# SMPS_2018_09_04_A.net
KiCad netlist of a schematic drawn in EAGLE
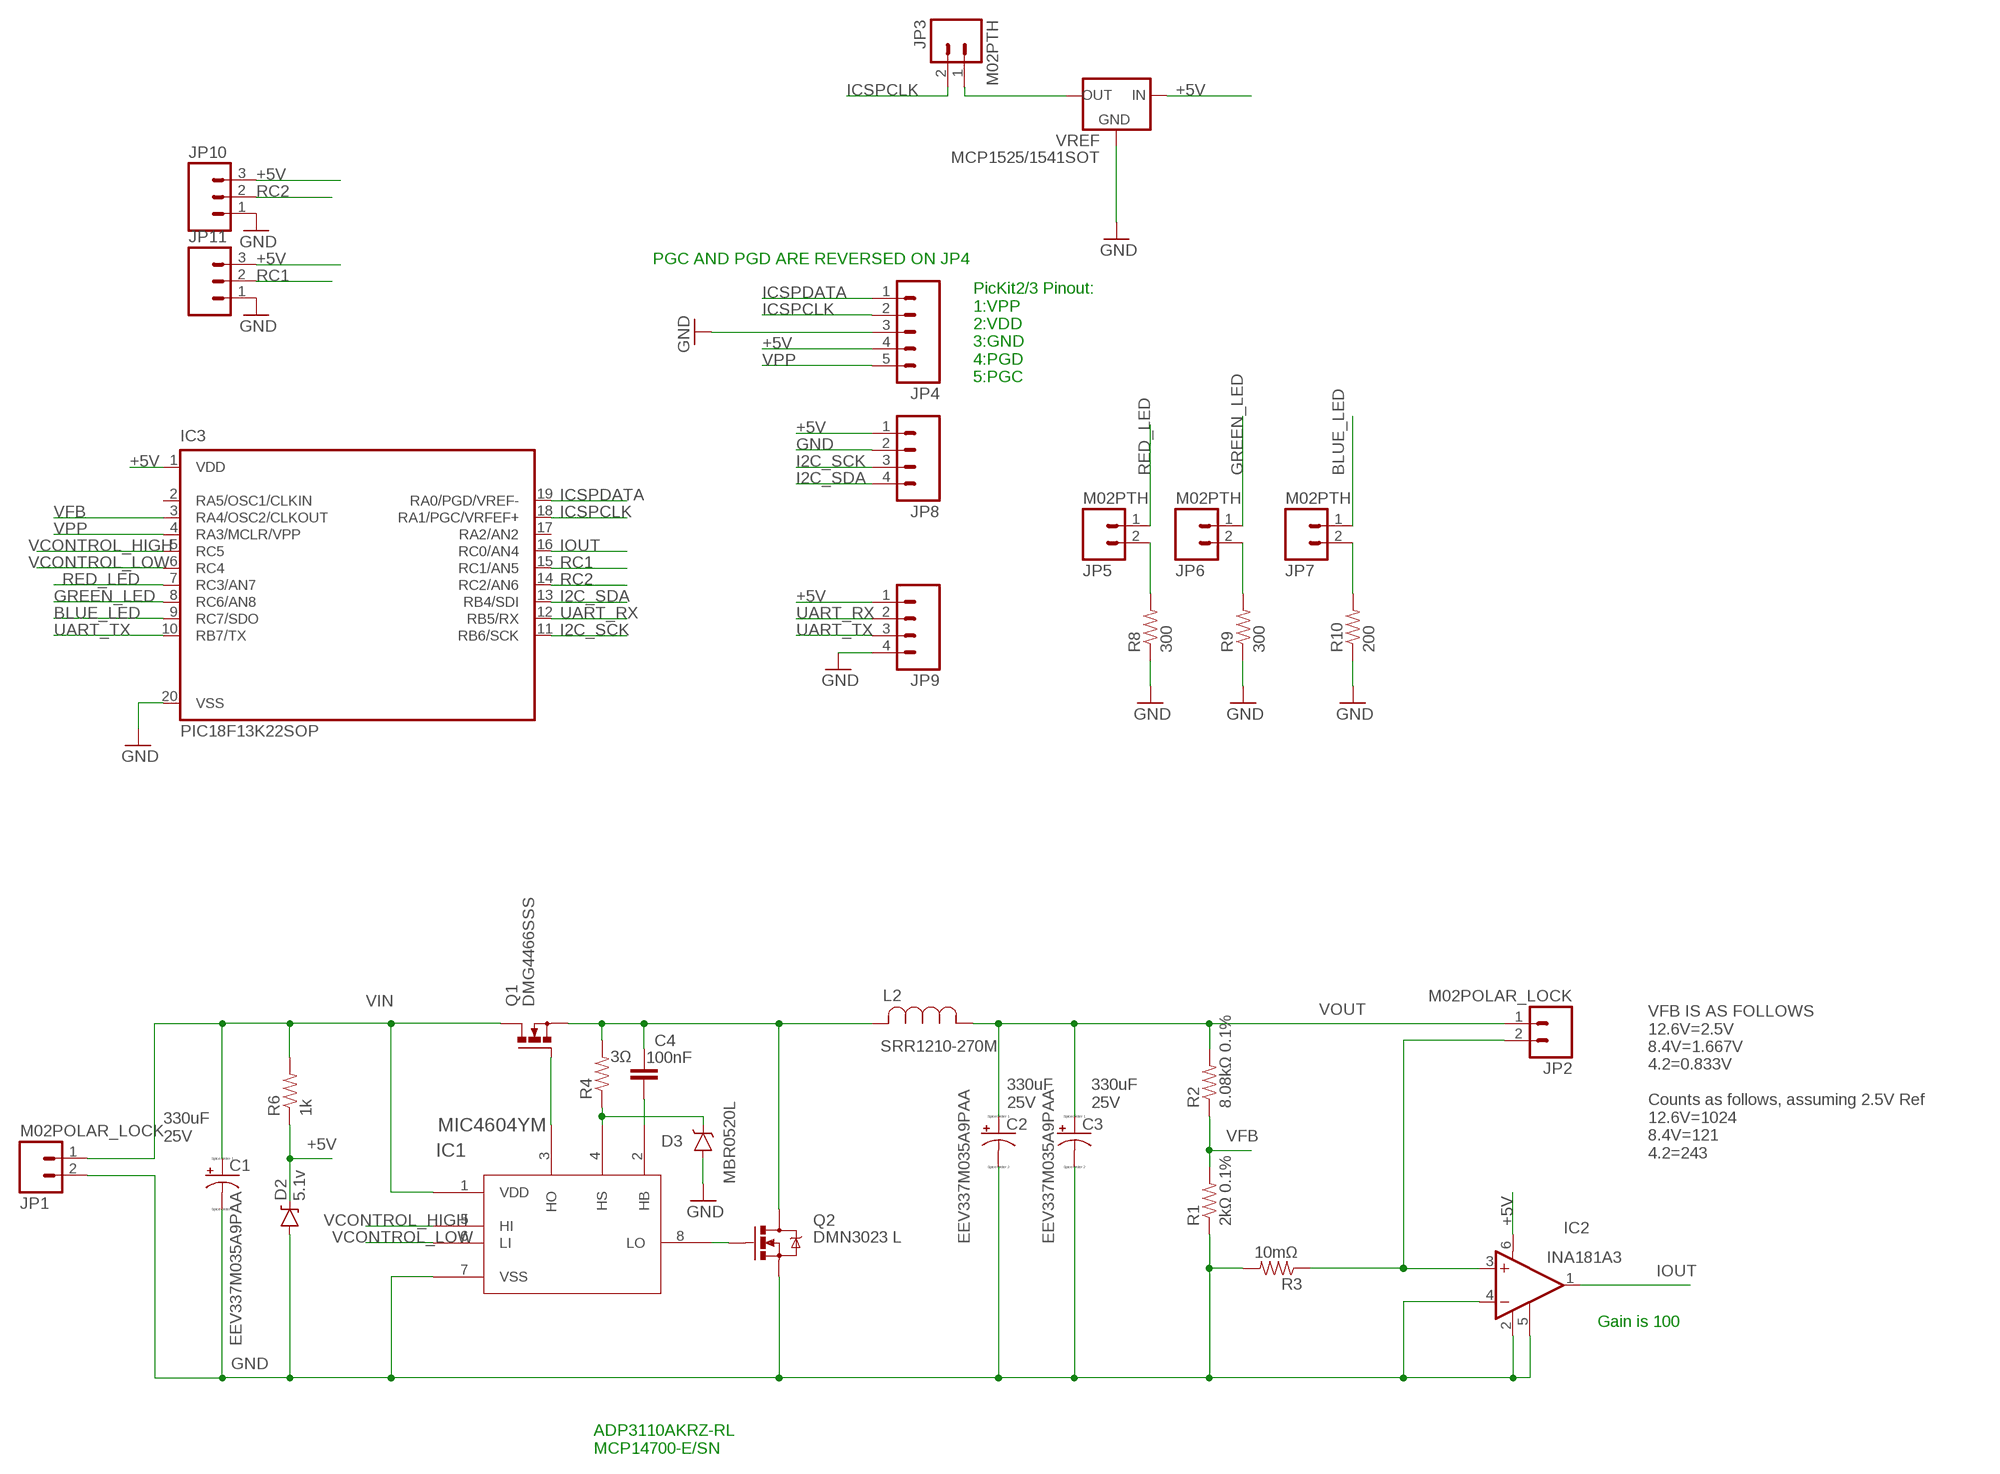
[diagram p0: schematic, sheet 1]

(export (version "E")
  (design (tool "Eeschema 10.0.6"))
  (components
    (comp (ref "C1")
      (value "EEV337M035A9PAA")
      (footprint "eagle-import:140CLH-1010")
      (libsource (lib "eagle-import") (part "CPOL-US140CLH-1010"))
    )
    (comp (ref "C2")
      (value "EEV337M035A9PAA")
      (footprint "eagle-import:140CLH-1010")
      (libsource (lib "eagle-import") (part "CPOL-US140CLH-1010"))
    )
    (comp (ref "C3")
      (value "EEV337M035A9PAA")
      (footprint "eagle-import:140CLH-1010")
      (libsource (lib "eagle-import") (part "CPOL-US140CLH-1010"))
    )
    (comp (ref "C4")
      (value "100nF")
      (footprint "eagle-import:1206")
      (libsource (lib "eagle-import") (part "CAP1206"))
    )
    (comp (ref "D2")
      (value "5.1v")
      (footprint "eagle-import:SMB-DIODE")
      (libsource (lib "eagle-import") (part "DIODE-ZENERSMB"))
    )
    (comp (ref "D3")
      (value "MBR0520L")
      (footprint "eagle-import:SMA-DIODE")
      (libsource (lib "eagle-import") (part "DIODE-SCHOTTKY-B340A"))
    )
    (comp (ref "IC1")
      (value "MIC4604YM")
      (footprint "eagle-import:SOIC-8_M")
      (fields (field (name "MANUFACTURER_PART_NUMBER") "mic4604ym"))
      (libsource (lib "eagle-import") (part "MIC4604YM"))
    )
    (comp (ref "IC2")
      (value "INA181A3")
      (footprint "eagle-import:SOT23-6")
      (libsource (lib "eagle-import") (part "INA181A3"))
    )
    (comp (ref "IC3")
      (value "PIC18F13K22SOP")
      (footprint "eagle-import:SOP20W")
      (libsource (lib "eagle-import") (part "PIC18F13K22?SOP"))
    )
    (comp (ref "JP1")
      (value "M02POLAR_LOCK")
      (footprint "eagle-import:MOLEX-1X2_LOCK")
      (libsource (lib "eagle-import") (part "M02POLAR_LOCK"))
    )
    (comp (ref "JP2")
      (value "M02POLAR_LOCK")
      (footprint "eagle-import:MOLEX-1X2_LOCK")
      (libsource (lib "eagle-import") (part "M02POLAR_LOCK"))
    )
    (comp (ref "JP3")
      (value "M02PTH")
      (footprint "eagle-import:1X02")
      (libsource (lib "eagle-import") (part "M02PTH"))
    )
    (comp (ref "JP4")
      (value "M05PTH_LONGPADS")
      (footprint "eagle-import:1X05_LONGPADS")
      (libsource (lib "eagle-import") (part "M05PTH_LONGPADS"))
    )
    (comp (ref "JP5")
      (value "M02PTH")
      (footprint "eagle-import:1X02")
      (libsource (lib "eagle-import") (part "M02PTH"))
    )
    (comp (ref "JP6")
      (value "M02PTH")
      (footprint "eagle-import:1X02")
      (libsource (lib "eagle-import") (part "M02PTH"))
    )
    (comp (ref "JP7")
      (value "M02PTH")
      (footprint "eagle-import:1X02")
      (libsource (lib "eagle-import") (part "M02PTH"))
    )
    (comp (ref "JP8")
      (value "M04LOCK")
      (footprint "eagle-import:1X04_LOCK")
      (libsource (lib "eagle-import") (part "M04LOCK"))
    )
    (comp (ref "JP9")
      (value "M04LOCK")
      (footprint "eagle-import:1X04_LOCK")
      (libsource (lib "eagle-import") (part "M04LOCK"))
    )
    (comp (ref "JP10")
      (value "M03LOCK")
      (footprint "eagle-import:1X03_LOCK")
      (libsource (lib "eagle-import") (part "M03LOCK"))
    )
    (comp (ref "JP11")
      (value "M03LOCK")
      (footprint "eagle-import:1X03_LOCK")
      (libsource (lib "eagle-import") (part "M03LOCK"))
    )
    (comp (ref "L2")
      (value "SRR1210-270M")
      (footprint "eagle-import:IND_BOURNS_SRR1210")
      (fields (field (name "MANUFACTURER_PART_NUMBER") "SRR1210680M"))
      (libsource (lib "eagle-import") (part "SRR1210-680M"))
    )
    (comp (ref "Q1")
      (value "DMG4466SSS")
      (footprint "eagle-import:SO-08")
      (libsource (lib "eagle-import") (part "N-MOSFET-SO8S"))
    )
    (comp (ref "Q2")
      (value "DMN3023 L")
      (footprint "eagle-import:SOT23-3")
      (libsource (lib "eagle-import") (part "MOSFET-NCHANNELBSS123LT1G"))
    )
    (comp (ref "R1")
      (value "2kΩ 0.1%")
      (footprint "eagle-import:1206")
      (libsource (lib "eagle-import") (part "RESISTOR1206"))
    )
    (comp (ref "R2")
      (value "8.08kΩ 0.1%")
      (footprint "eagle-import:1206")
      (libsource (lib "eagle-import") (part "RESISTOR1206"))
    )
    (comp (ref "R3")
      (value "10mΩ")
      (footprint "eagle-import:1206")
      (libsource (lib "eagle-import") (part "RESISTOR1206"))
    )
    (comp (ref "R4")
      (value "3Ω")
      (footprint "eagle-import:1206")
      (libsource (lib "eagle-import") (part "RESISTOR1206"))
    )
    (comp (ref "R6")
      (value "1k")
      (footprint "eagle-import:1206")
      (libsource (lib "eagle-import") (part "RESISTOR1206"))
    )
    (comp (ref "R8")
      (value "300")
      (footprint "eagle-import:1206")
      (libsource (lib "eagle-import") (part "RESISTOR1206"))
    )
    (comp (ref "R9")
      (value "300")
      (footprint "eagle-import:1206")
      (libsource (lib "eagle-import") (part "RESISTOR1206"))
    )
    (comp (ref "R10")
      (value "200")
      (footprint "eagle-import:1206")
      (libsource (lib "eagle-import") (part "RESISTOR1206"))
    )
    (comp (ref "VREF")
      (value "MCP1525/1541SOT")
      (footprint "eagle-import:SOT23-3")
      (libsource (lib "eagle-import") (part "MCP1525/1541SOT"))
    )
  )
  (nets
    (net (code "1") (name "/+5V") (class "Default")
      (node (ref "D2") (pin "C") (pinfunction "C_C") (pintype "passive"))
      (node (ref "IC2") (pin "6") (pinfunction "V+_6") (pintype "power_in"))
      (node (ref "IC3") (pin "1") (pinfunction "VDD_1") (pintype "power_in"))
      (node (ref "JP10") (pin "3") (pinfunction "3_3") (pintype "passive"))
      (node (ref "JP11") (pin "3") (pinfunction "3_3") (pintype "passive"))
      (node (ref "JP4") (pin "4") (pinfunction "4_4") (pintype "passive"))
      (node (ref "JP8") (pin "1") (pinfunction "1_1") (pintype "passive"))
      (node (ref "JP9") (pin "1") (pinfunction "1_1") (pintype "passive"))
      (node (ref "R6") (pin "1") (pinfunction "1_1") (pintype "passive"))
      (node (ref "VREF") (pin "1") (pinfunction "IN_1") (pintype "input"))
    )
    (net (code "2") (name "/BLUE_LED") (class "Default")
      (node (ref "IC3") (pin "9") (pinfunction "RC7/SDO_9") (pintype "bidirectional"))
      (node (ref "JP7") (pin "1") (pinfunction "1_1") (pintype "passive"))
    )
    (net (code "3") (name "/GREEN_LED") (class "Default")
      (node (ref "IC3") (pin "8") (pinfunction "RC6/AN8_8") (pintype "bidirectional"))
      (node (ref "JP6") (pin "1") (pinfunction "1_1") (pintype "passive"))
    )
    (net (code "4") (name "/I2C_SCK") (class "Default")
      (node (ref "IC3") (pin "11") (pinfunction "RB6/SCK_11") (pintype "bidirectional"))
      (node (ref "JP8") (pin "3") (pinfunction "3_3") (pintype "passive"))
    )
    (net (code "5") (name "/I2C_SDA") (class "Default")
      (node (ref "IC3") (pin "13") (pinfunction "RB4/SDI_13") (pintype "bidirectional"))
      (node (ref "JP8") (pin "4") (pinfunction "4_4") (pintype "passive"))
    )
    (net (code "6") (name "/ICSPCLK") (class "Default")
      (node (ref "IC3") (pin "18") (pinfunction "RA1/PGC/VRFEF+_18") (pintype "bidirectional"))
      (node (ref "JP3") (pin "2") (pinfunction "2_2") (pintype "passive"))
      (node (ref "JP4") (pin "2") (pinfunction "2_2") (pintype "passive"))
    )
    (net (code "7") (name "/ICSPDATA") (class "Default")
      (node (ref "IC3") (pin "19") (pinfunction "RA0/PGD/VREF-_19") (pintype "bidirectional"))
      (node (ref "JP4") (pin "1") (pinfunction "1_1") (pintype "passive"))
    )
    (net (code "8") (name "/IOUT") (class "Default")
      (node (ref "IC2") (pin "1") (pinfunction "OUT_1") (pintype "output"))
      (node (ref "IC3") (pin "16") (pinfunction "RC0/AN4_16") (pintype "bidirectional"))
    )
    (net (code "9") (name "/RC1") (class "Default")
      (node (ref "IC3") (pin "15") (pinfunction "RC1/AN5_15") (pintype "bidirectional"))
      (node (ref "JP11") (pin "2") (pinfunction "2_2") (pintype "passive"))
    )
    (net (code "10") (name "/RC2") (class "Default")
      (node (ref "IC3") (pin "14") (pinfunction "RC2/AN6_14") (pintype "bidirectional"))
      (node (ref "JP10") (pin "2") (pinfunction "2_2") (pintype "passive"))
    )
    (net (code "11") (name "/RED_LED") (class "Default")
      (node (ref "IC3") (pin "7") (pinfunction "RC3/AN7_7") (pintype "bidirectional"))
      (node (ref "JP5") (pin "1") (pinfunction "1_1") (pintype "passive"))
    )
    (net (code "12") (name "/UART_RX") (class "Default")
      (node (ref "IC3") (pin "12") (pinfunction "RB5/RX_12") (pintype "bidirectional"))
      (node (ref "JP9") (pin "2") (pinfunction "2_2") (pintype "passive"))
    )
    (net (code "13") (name "/UART_TX") (class "Default")
      (node (ref "IC3") (pin "10") (pinfunction "RB7/TX_10") (pintype "bidirectional"))
      (node (ref "JP9") (pin "3") (pinfunction "3_3") (pintype "passive"))
    )
    (net (code "14") (name "/VCONTROL_HIGH") (class "Default")
      (node (ref "IC1") (pin "5") (pinfunction "HI_5") (pintype "input"))
      (node (ref "IC3") (pin "5") (pinfunction "RC5_5") (pintype "bidirectional"))
    )
    (net (code "15") (name "/VCONTROL_LOW") (class "Default")
      (node (ref "IC1") (pin "6") (pinfunction "LI_6") (pintype "input"))
      (node (ref "IC3") (pin "6") (pinfunction "RC4_6") (pintype "bidirectional"))
    )
    (net (code "16") (name "/VFB") (class "Default")
      (node (ref "IC3") (pin "3") (pinfunction "RA4/OSC2/CLKOUT_3") (pintype "bidirectional"))
      (node (ref "R1") (pin "2") (pinfunction "2_2") (pintype "passive"))
      (node (ref "R2") (pin "1") (pinfunction "1_1") (pintype "passive"))
    )
    (net (code "17") (name "/VIN") (class "Default")
      (node (ref "C1") (pin "+") (pinfunction "+_+") (pintype "passive"))
      (node (ref "IC1") (pin "1") (pinfunction "VDD_1") (pintype "power_in"))
      (node (ref "JP1") (pin "1") (pinfunction "1_1") (pintype "passive"))
      (node (ref "Q1") (pin "5") (pinfunction "D_5") (pintype "passive"))
      (node (ref "Q1") (pin "6") (pinfunction "D_6") (pintype "passive"))
      (node (ref "Q1") (pin "7") (pinfunction "D_7") (pintype "passive"))
      (node (ref "Q1") (pin "8") (pinfunction "D_8") (pintype "passive"))
      (node (ref "R6") (pin "2") (pinfunction "2_2") (pintype "passive"))
    )
    (net (code "18") (name "/VOUT") (class "Default")
      (node (ref "C2") (pin "+") (pinfunction "+_+") (pintype "passive"))
      (node (ref "C3") (pin "+") (pinfunction "+_+") (pintype "passive"))
      (node (ref "JP2") (pin "1") (pinfunction "1_1") (pintype "passive"))
      (node (ref "L2") (pin "1") (pinfunction "1_1") (pintype "passive"))
      (node (ref "R2") (pin "2") (pinfunction "2_2") (pintype "passive"))
    )
    (net (code "19") (name "/VPP") (class "Default")
      (node (ref "IC3") (pin "4") (pinfunction "RA3/MCLR/VPP_4") (pintype "bidirectional"))
      (node (ref "JP4") (pin "5") (pinfunction "5_5") (pintype "passive"))
    )
    (net (code "20") (name "GND") (class "Default")
      (node (ref "C1") (pin "-") (pinfunction "-_-") (pintype "passive"))
      (node (ref "C2") (pin "-") (pinfunction "-_-") (pintype "passive"))
      (node (ref "C3") (pin "-") (pinfunction "-_-") (pintype "passive"))
      (node (ref "D2") (pin "A") (pinfunction "A_A") (pintype "passive"))
      (node (ref "D3") (pin "A") (pinfunction "A_A") (pintype "passive"))
      (node (ref "IC1") (pin "7") (pinfunction "VSS_7") (pintype "power_in"))
      (node (ref "IC2") (pin "2") (pinfunction "GND_2") (pintype "power_in"))
      (node (ref "IC2") (pin "4") (pinfunction "-IN_4") (pintype "input"))
      (node (ref "IC2") (pin "5") (pinfunction "REF_5") (pintype "bidirectional"))
      (node (ref "IC3") (pin "20") (pinfunction "VSS_20") (pintype "power_in"))
      (node (ref "JP1") (pin "2") (pinfunction "2_2") (pintype "passive"))
      (node (ref "JP10") (pin "1") (pinfunction "1_1") (pintype "passive"))
      (node (ref "JP11") (pin "1") (pinfunction "1_1") (pintype "passive"))
      (node (ref "JP4") (pin "3") (pinfunction "3_3") (pintype "passive"))
      (node (ref "JP8") (pin "2") (pinfunction "2_2") (pintype "passive"))
      (node (ref "JP9") (pin "4") (pinfunction "4_4") (pintype "passive"))
      (node (ref "Q2") (pin "2") (pinfunction "S_2") (pintype "passive"))
      (node (ref "R1") (pin "1") (pinfunction "1_1") (pintype "passive"))
      (node (ref "R10") (pin "1") (pinfunction "1_1") (pintype "passive"))
      (node (ref "R3") (pin "2") (pinfunction "2_2") (pintype "passive"))
      (node (ref "R8") (pin "1") (pinfunction "1_1") (pintype "passive"))
      (node (ref "R9") (pin "1") (pinfunction "1_1") (pintype "passive"))
      (node (ref "VREF") (pin "3") (pinfunction "GND_3") (pintype "input"))
    )
    (net (code "21") (name "Net-(IC1-HB)") (class "Default")
      (node (ref "C4") (pin "1") (pinfunction "1_1") (pintype "passive"))
      (node (ref "IC1") (pin "2") (pinfunction "HB_2") (pintype "passive"))
    )
    (net (code "22") (name "Net-(IC1-HO)") (class "Default")
      (node (ref "IC1") (pin "3") (pinfunction "HO_3") (pintype "output"))
      (node (ref "Q1") (pin "4") (pinfunction "G_4") (pintype "passive"))
    )
    (net (code "23") (name "Net-(IC1-HS)") (class "Default")
      (node (ref "D3") (pin "C") (pinfunction "C_C") (pintype "passive"))
      (node (ref "IC1") (pin "4") (pinfunction "HS_4") (pintype "passive"))
      (node (ref "R4") (pin "1") (pinfunction "1_1") (pintype "passive"))
    )
    (net (code "24") (name "Net-(IC1-LO)") (class "Default")
      (node (ref "IC1") (pin "8") (pinfunction "LO_8") (pintype "output"))
      (node (ref "Q2") (pin "1") (pinfunction "G_1") (pintype "passive"))
    )
    (net (code "25") (name "Net-(IC2-+IN)") (class "Default")
      (node (ref "IC2") (pin "3") (pinfunction "+IN_3") (pintype "input"))
      (node (ref "JP2") (pin "2") (pinfunction "2_2") (pintype "passive"))
      (node (ref "R3") (pin "1") (pinfunction "1_1") (pintype "passive"))
    )
    (net (code "26") (name "Net-(JP5-Pad2)") (class "Default")
      (node (ref "JP5") (pin "2") (pinfunction "2_2") (pintype "passive"))
      (node (ref "R8") (pin "2") (pinfunction "2_2") (pintype "passive"))
    )
    (net (code "27") (name "Net-(JP6-Pad2)") (class "Default")
      (node (ref "JP6") (pin "2") (pinfunction "2_2") (pintype "passive"))
      (node (ref "R9") (pin "2") (pinfunction "2_2") (pintype "passive"))
    )
    (net (code "28") (name "Net-(JP7-Pad2)") (class "Default")
      (node (ref "JP7") (pin "2") (pinfunction "2_2") (pintype "passive"))
      (node (ref "R10") (pin "2") (pinfunction "2_2") (pintype "passive"))
    )
    (net (code "29") (name "Net-(Q2-D)") (class "Default")
      (node (ref "C4") (pin "2") (pinfunction "2_2") (pintype "passive"))
      (node (ref "L2") (pin "2") (pinfunction "2_2") (pintype "passive"))
      (node (ref "Q1") (pin "1") (pinfunction "S_1") (pintype "passive"))
      (node (ref "Q1") (pin "2") (pinfunction "S_2") (pintype "passive"))
      (node (ref "Q1") (pin "3") (pinfunction "S_3") (pintype "passive"))
      (node (ref "Q2") (pin "3") (pinfunction "D_3") (pintype "passive"))
      (node (ref "R4") (pin "2") (pinfunction "2_2") (pintype "passive"))
    )
    (net (code "30") (name "Net-(VREF-OUT)") (class "Default")
      (node (ref "JP3") (pin "1") (pinfunction "1_1") (pintype "passive"))
      (node (ref "VREF") (pin "2") (pinfunction "OUT_2") (pintype "output"))
    )
    (net (code "31") (name "unconnected-(IC3-RA2{slash}AN2-Pad17)") (class "Default")
      (node (ref "IC3") (pin "17") (pinfunction "RA2/AN2_17") (pintype "bidirectional"))
    )
    (net (code "32") (name "unconnected-(IC3-RA5{slash}OSC1{slash}CLKIN-Pad2)") (class "Default")
      (node (ref "IC3") (pin "2") (pinfunction "RA5/OSC1/CLKIN_2") (pintype "bidirectional"))
    )
  )
)
